# Voltage_Regulation.net
KiCad netlist of a schematic drawn in EAGLE
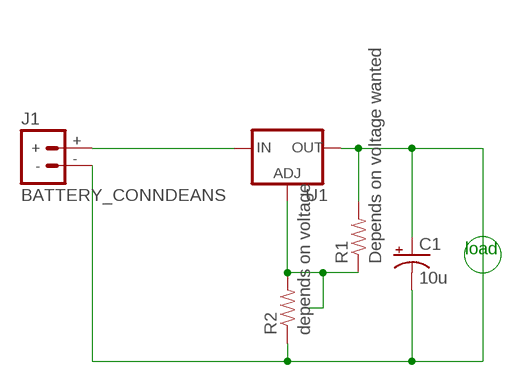
[diagram p0: schematic, sheet 1]

(export (version "E")
  (design (tool "Eeschema 10.0.6"))
  (components
    (comp (ref "C1")
      (value "10u")
      (footprint "eagle-import:CPOL-RADIAL-10UF-25V")
      (libsource (lib "eagle-import") (part "CAP_POLPTH2"))
    )
    (comp (ref "J1")
      (value "BATTERY_CONNDEANS")
      (footprint "eagle-import:DEANS")
      (libsource (lib "eagle-import") (part "BATTERY_CONNDEANS"))
    )
    (comp (ref "R1")
      (value "Depends on voltage wanted")
      (footprint "eagle-import:AXIAL-0.5")
      (libsource (lib "eagle-import") (part "RESISTORPTH-1/2W"))
    )
    (comp (ref "R2")
      (value "depends on voltage")
      (footprint "eagle-import:AXIAL-0.5")
      (libsource (lib "eagle-import") (part "RESISTORPTH-1/2W"))
    )
    (comp (ref "U1")
      (value "V_REG_317DPACK")
      (footprint "eagle-import:V-REG_DPACK")
      (libsource (lib "eagle-import") (part "V_REG_317DPACK"))
    )
  )
  (nets
    (net (code "1") (name "Net-(C1-+)") (class "Default")
      (node (ref "C1") (pin "1") (pinfunction "+_1") (pintype "passive"))
      (node (ref "C1") (pin "2") (pinfunction "-_2") (pintype "passive"))
      (node (ref "J1") (pin "-") (pinfunction "-_-") (pintype "passive"))
      (node (ref "R1") (pin "P$2") (pinfunction "2_P$2") (pintype "passive"))
      (node (ref "R2") (pin "P$1") (pinfunction "1_P$1") (pintype "passive"))
      (node (ref "U1") (pin "4") (pinfunction "OUT_4") (pintype "output"))
    )
    (net (code "2") (name "Net-(R1-1)") (class "Default")
      (node (ref "R1") (pin "P$1") (pinfunction "1_P$1") (pintype "passive"))
      (node (ref "R2") (pin "P$2") (pinfunction "2_P$2") (pintype "passive"))
      (node (ref "U1") (pin "1") (pinfunction "ADJ_1") (pintype "input"))
    )
    (net (code "3") (name "Net-(U1-IN)") (class "Default")
      (node (ref "J1") (pin "+") (pinfunction "+_+") (pintype "passive"))
      (node (ref "U1") (pin "3") (pinfunction "IN_3") (pintype "input"))
    )
  )
)
